# boost-test-2.net
KiCad netlist of a schematic drawn in EAGLE
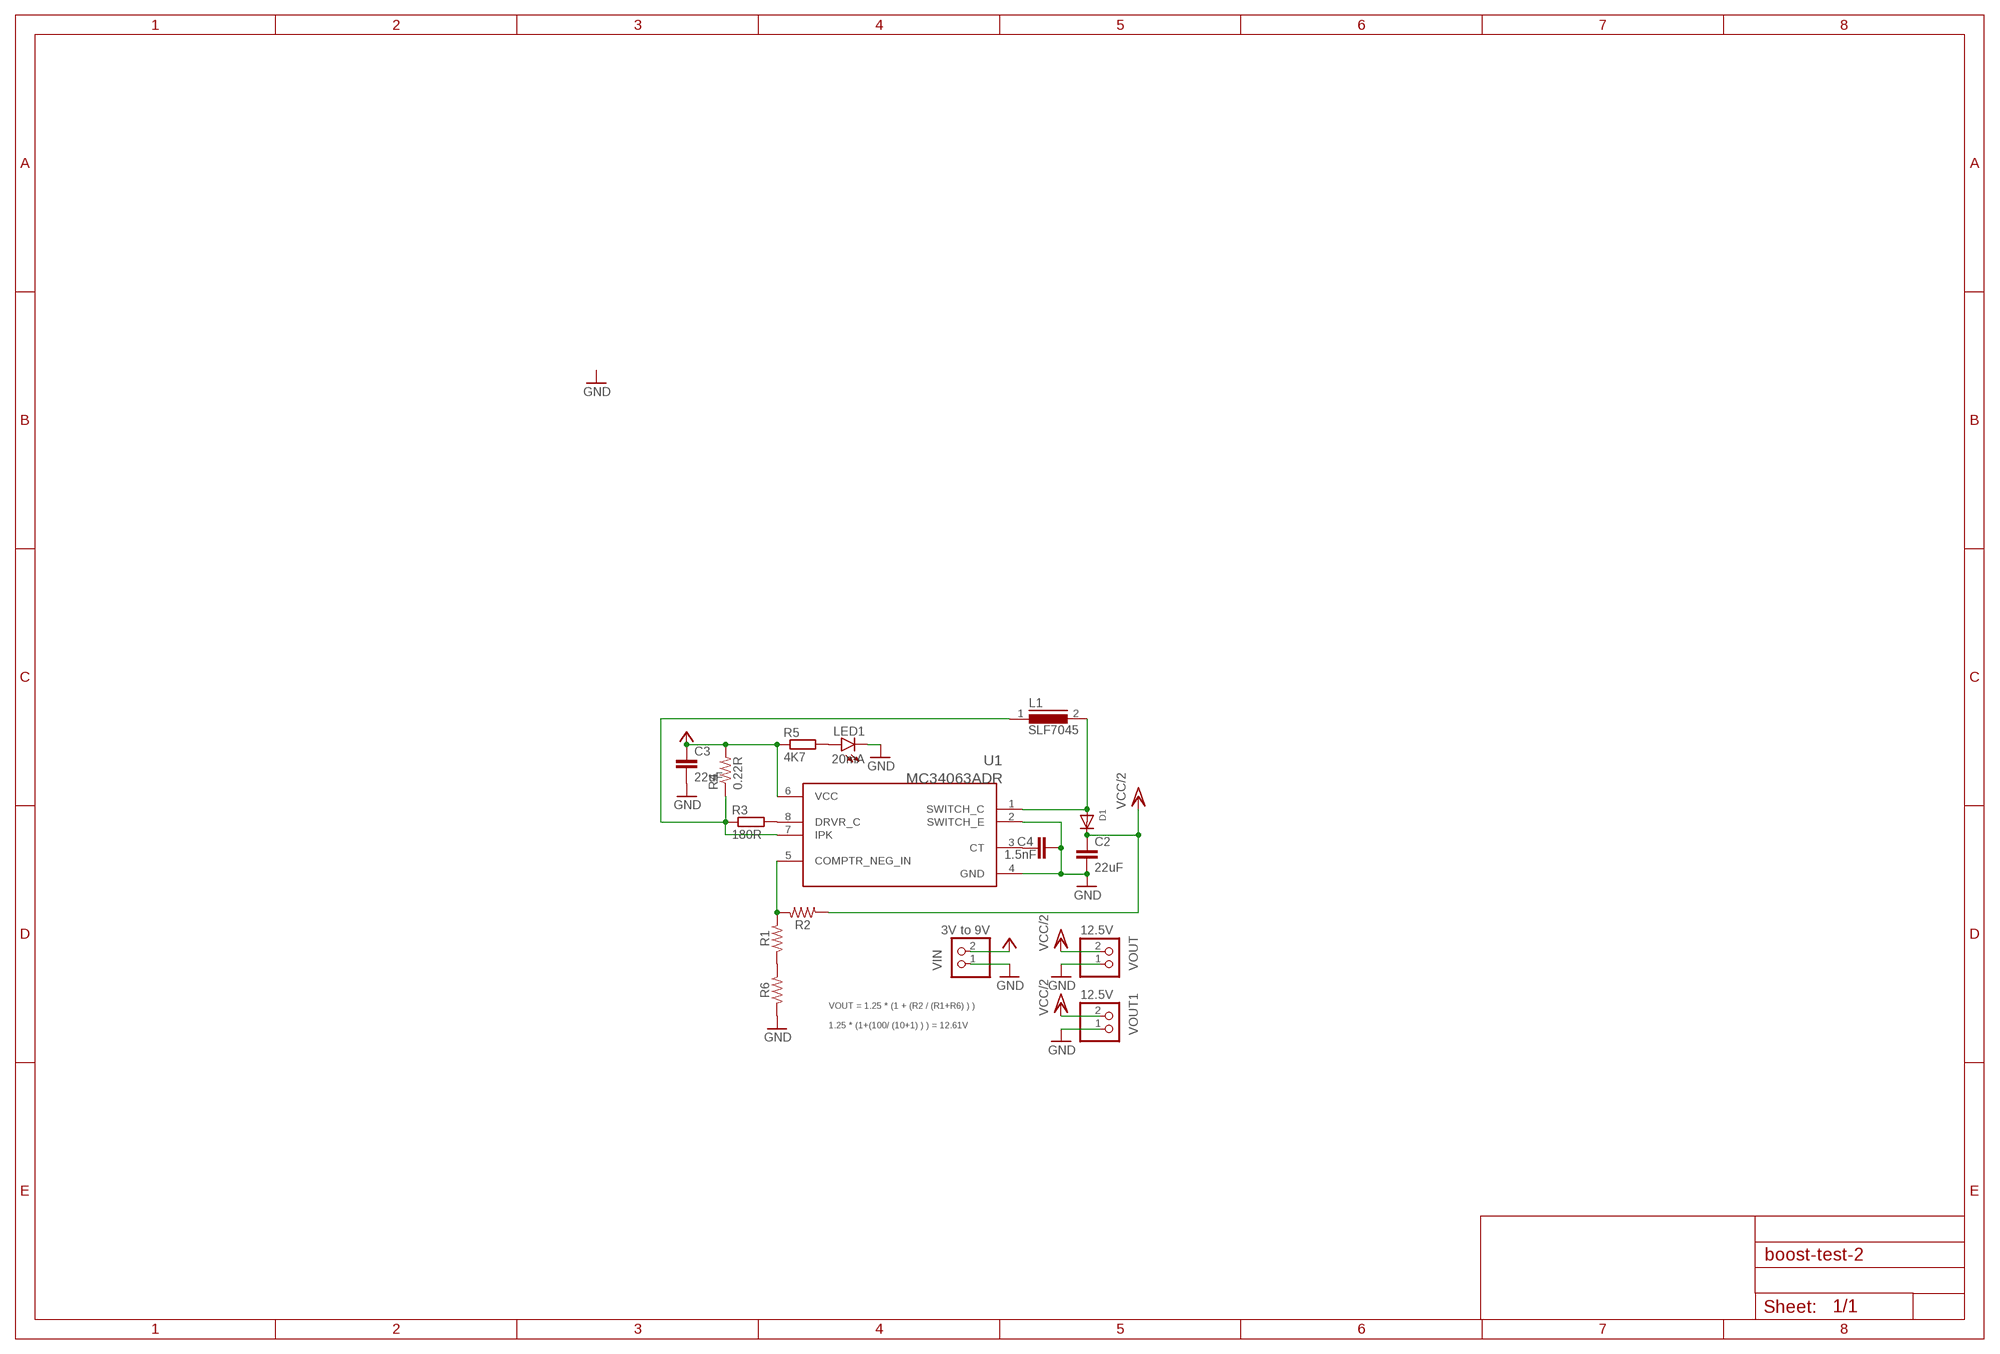
[diagram p0: schematic, sheet 1]

(export (version "E")
  (design (tool "Eeschema 10.0.6"))
  (components
    (comp (ref "C2")
      (value "22uF")
      (footprint "eagle-import:0805")
      (libsource (lib "eagle-import") (part "22UF-0805-6.3V-20%"))
    )
    (comp (ref "C3")
      (value "22uF")
      (footprint "eagle-import:0805")
      (libsource (lib "eagle-import") (part "22UF-0805-6.3V-20%"))
    )
    (comp (ref "C4")
      (value "1.5nF")
      (footprint "eagle-import:C0603")
      (libsource (lib "eagle-import") (part "C-EUC0603"))
    )
    (comp (ref "D1")
      (value "ADAFRUIT_DIODESOD-123")
      (footprint "eagle-import:ADAFRUIT_SOD-123")
      (libsource (lib "eagle-import") (part "ADAFRUIT_DIODESOD-123"))
    )
    (comp (ref "L1")
      (value "SLF7045")
      (footprint "eagle-import:SLF7045")
      (libsource (lib "eagle-import") (part "SLF7045"))
    )
    (comp (ref "LED1")
      (value "20mA")
      (footprint "eagle-import:CHIP-LED0603")
      (libsource (lib "eagle-import") (part "LEDCHIP-LED0603"))
    )
    (comp (ref "R1")
      (value "10K")
      (footprint "eagle-import:52101-101-REV-A_RC-MASTER-SMD_R0603MP")
      (libsource (lib "eagle-import") (part "52101-101-REV-A_RC-MASTER-SMD_R_0603MP"))
    )
    (comp (ref "R2")
      (value "100K")
      (footprint "eagle-import:52101-101-REV-A_RC-MASTER-SMD_R0603MP")
      (libsource (lib "eagle-import") (part "52101-101-REV-A_RC-MASTER-SMD_R_0603MP"))
    )
    (comp (ref "R3")
      (value "180R")
      (footprint "eagle-import:R0402")
      (libsource (lib "eagle-import") (part "R-EU_R0402"))
    )
    (comp (ref "R4")
      (value "0.22R")
      (footprint "eagle-import:M0805")
      (libsource (lib "eagle-import") (part "R-US_M0805"))
    )
    (comp (ref "R5")
      (value "4K7")
      (footprint "eagle-import:R0402")
      (libsource (lib "eagle-import") (part "R-EU_R0402"))
    )
    (comp (ref "R6")
      (value "1K")
      (footprint "eagle-import:52101-101-REV-A_RC-MASTER-SMD_R0603MP")
      (libsource (lib "eagle-import") (part "52101-101-REV-A_RC-MASTER-SMD_R_0603MP"))
    )
    (comp (ref "U1")
      (value "MC34063ADR")
      (footprint "eagle-import:SOIC127P599X175-8N")
      (fields (field (name "MF") "Texas Instruments"))
      (libsource (lib "eagle-import") (part "MC34063ADR"))
    )
    (comp (ref "VIN")
      (value "3V to 9V")
      (footprint "eagle-import:1X02")
      (libsource (lib "eagle-import") (part "PINHD-1X2"))
    )
    (comp (ref "VOUT")
      (value "12.5V")
      (footprint "eagle-import:1X02")
      (libsource (lib "eagle-import") (part "PINHD-1X2"))
    )
    (comp (ref "VOUT1")
      (value "12.5V")
      (footprint "eagle-import:1X02")
      (libsource (lib "eagle-import") (part "PINHD-1X2"))
    )
  )
  (nets
    (net (code "1") (name "GND") (class "Default")
      (node (ref "C2") (pin "2") (pinfunction "2_2") (pintype "passive"))
      (node (ref "C3") (pin "2") (pinfunction "2_2") (pintype "passive"))
      (node (ref "C4") (pin "1") (pinfunction "1_1") (pintype "passive"))
      (node (ref "LED1") (pin "C") (pinfunction "C_C") (pintype "passive"))
      (node (ref "R6") (pin "1") (pinfunction "1_1") (pintype "passive"))
      (node (ref "U1") (pin "2") (pinfunction "SWITCH_E_2") (pintype "bidirectional"))
      (node (ref "U1") (pin "4") (pinfunction "GND_4") (pintype "power_in"))
      (node (ref "VIN") (pin "1") (pinfunction "1_1") (pintype "passive"))
      (node (ref "VOUT") (pin "1") (pinfunction "1_1") (pintype "passive"))
      (node (ref "VOUT1") (pin "1") (pinfunction "1_1") (pintype "passive"))
    )
    (net (code "2") (name "Net-(LED1-PadA)") (class "Default")
      (node (ref "LED1") (pin "A") (pinfunction "A_A") (pintype "passive"))
      (node (ref "R5") (pin "2") (pinfunction "2_2") (pintype "passive"))
    )
    (net (code "3") (name "Net-(R1-Pad1)") (class "Default")
      (node (ref "R1") (pin "1") (pinfunction "1_1") (pintype "passive"))
      (node (ref "R6") (pin "2") (pinfunction "2_2") (pintype "passive"))
    )
    (net (code "4") (name "Net-(U1-COMPTR_NEG_IN)") (class "Default")
      (node (ref "R1") (pin "2") (pinfunction "2_2") (pintype "passive"))
      (node (ref "R2") (pin "2") (pinfunction "2_2") (pintype "passive"))
      (node (ref "U1") (pin "5") (pinfunction "COMPTR_NEG_IN_5") (pintype "input"))
    )
    (net (code "5") (name "Net-(U1-CT)") (class "Default")
      (node (ref "C4") (pin "2") (pinfunction "2_2") (pintype "passive"))
      (node (ref "U1") (pin "3") (pinfunction "CT_3") (pintype "passive"))
    )
    (net (code "6") (name "Net-(U1-DRVR_C)") (class "Default")
      (node (ref "R3") (pin "2") (pinfunction "2_2") (pintype "passive"))
      (node (ref "U1") (pin "8") (pinfunction "DRVR_C_8") (pintype "bidirectional"))
    )
    (net (code "7") (name "Net-(U1-IPK)") (class "Default")
      (node (ref "L1") (pin "1") (pinfunction "1_1") (pintype "passive"))
      (node (ref "R3") (pin "1") (pinfunction "1_1") (pintype "passive"))
      (node (ref "R4") (pin "1") (pinfunction "1_1") (pintype "passive"))
      (node (ref "U1") (pin "7") (pinfunction "IPK_7") (pintype "input"))
    )
    (net (code "8") (name "Net-(U1-SWITCH_C)") (class "Default")
      (node (ref "D1") (pin "A") (pinfunction "A_A") (pintype "passive"))
      (node (ref "L1") (pin "2") (pinfunction "2_2") (pintype "passive"))
      (node (ref "U1") (pin "1") (pinfunction "SWITCH_C_1") (pintype "bidirectional"))
    )
    (net (code "9") (name "VCC") (class "Default")
      (node (ref "C3") (pin "1") (pinfunction "1_1") (pintype "passive"))
      (node (ref "R4") (pin "2") (pinfunction "2_2") (pintype "passive"))
      (node (ref "R5") (pin "1") (pinfunction "1_1") (pintype "passive"))
      (node (ref "U1") (pin "6") (pinfunction "VCC_6") (pintype "power_in"))
      (node (ref "VIN") (pin "2") (pinfunction "2_2") (pintype "passive"))
    )
    (net (code "10") (name "VCC{slash}2") (class "Default")
      (node (ref "C2") (pin "1") (pinfunction "1_1") (pintype "passive"))
      (node (ref "D1") (pin "C") (pinfunction "C_C") (pintype "passive"))
      (node (ref "R2") (pin "1") (pinfunction "1_1") (pintype "passive"))
      (node (ref "VOUT") (pin "2") (pinfunction "2_2") (pintype "passive"))
      (node (ref "VOUT1") (pin "2") (pinfunction "2_2") (pintype "passive"))
    )
  )
)
